# Balance.net
KiCad netlist of a schematic drawn in Altium Designer
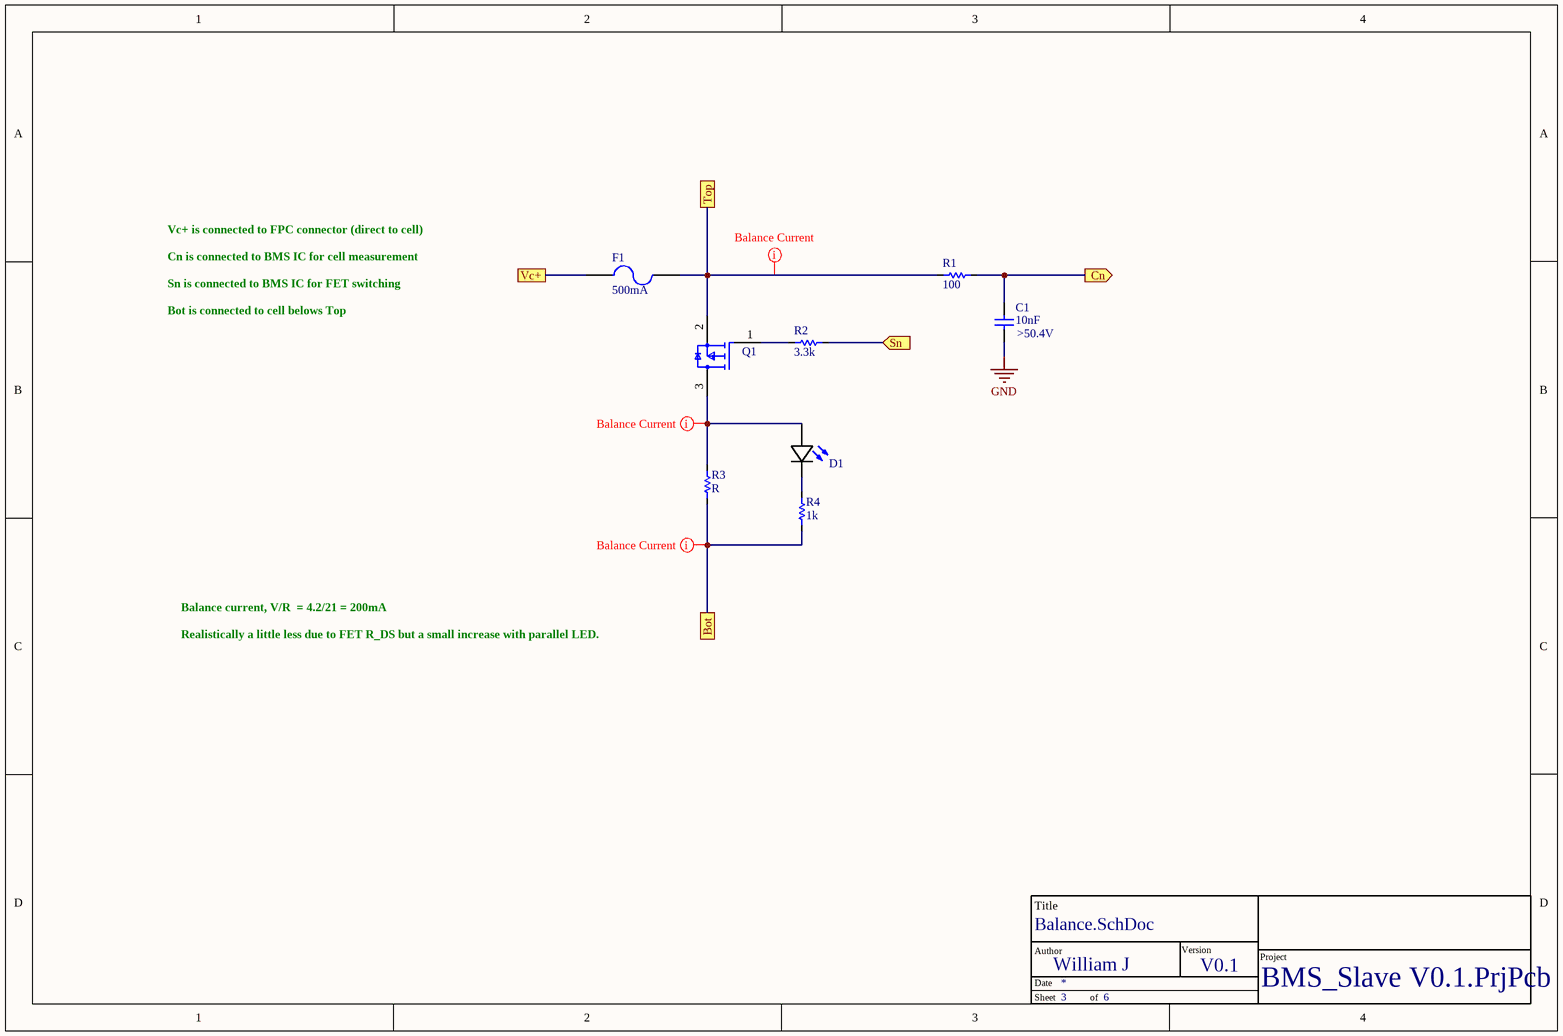
[diagram p0: Balance.SchDoc]

(export (version "E")
  (design (tool "Eeschema 10.0.6"))
  (components
    (comp (ref "*") (value "TitleBlock") (libsource (lib "SchematicLib") (part "TitleBlock")))
    (comp (ref "C1")
      (value "10nF")
      (footprint "C_0603")
      (description "Capacitor")
      (fields (field (name "VOLTAGE") ">50.4V") (field (name "Comment") "C"))
      (libsource (lib "Passives") (part "Capacitor"))
    )
    (comp (ref "D1")
      (value "150060BS55040")
      (footprint "LED (0603)")
      (description "LED BLUE DIFFUSED 0603 SMD")
      (fields (field (name "MANUFACTURER") "Wurth Electronics"))
      (libsource (lib "LEDLib") (part "150060BS55040"))
    )
    (comp (ref "F1")
      (value "0466.500NR")
      (footprint "0466.500NR")
      (fields
        (field (name "MANUFACTURER") "Littelfuse")
        (field (name "CURRENT RATING") "500mA")
        (field (name "PUBLISHER") "Altium Limited")
      )
      (libsource (lib "Miscellaneous Devices") (part "Fuse 2"))
    )
    (comp (ref "Q1")
      (value "NX2301P,215")
      (footprint "FP-SOT23-MFG")
      (description "MOSFET P-CH 20V 2A TO-236AB")
      (libsource (lib "Altium Content Vault") (part "882370683d780ecf8f33bea6fe01d97"))
    )
    (comp (ref "R1")
      (value "100")
      (footprint "R-0603")
      (description "Resistor")
      (libsource (lib "Passives") (part "Resistor"))
    )
    (comp (ref "R2")
      (value "3.3k")
      (footprint "R-0603")
      (description "Resistor")
      (libsource (lib "Passives") (part "Resistor"))
    )
    (comp (ref "R3")
      (value "R")
      (footprint "R_2512")
      (description "Resistor")
      (libsource (lib "Passives") (part "Resistor"))
    )
    (comp (ref "R4")
      (value "1k")
      (footprint "R-0603")
      (description "Resistor")
      (libsource (lib "Passives") (part "Resistor"))
    )
  )
  (nets
    (net (code "1") (name "/Bot") (class "Default")
      (node (ref "R3") (pin "1") (pinfunction "1_1") (pintype "passive"))
      (node (ref "R4") (pin "1") (pinfunction "1_1") (pintype "passive"))
    )
    (net (code "2") (name "/Cn") (class "Default")
      (node (ref "C1") (pin "2") (pinfunction "2_2") (pintype "passive"))
      (node (ref "R1") (pin "2") (pinfunction "2_2") (pintype "passive"))
    )
    (net (code "3") (name "/Sn") (class "Default")
      (node (ref "R2") (pin "2") (pinfunction "2_2") (pintype "passive"))
    )
    (net (code "4") (name "/Top") (class "Default")
      (node (ref "F1") (pin "2") (pinfunction "2_2") (pintype "passive"))
      (node (ref "Q1") (pin "2") (pinfunction "S_2") (pintype "passive"))
      (node (ref "R1") (pin "1") (pinfunction "1_1") (pintype "passive"))
    )
    (net (code "5") (name "/Vc+") (class "Default")
      (node (ref "F1") (pin "1") (pinfunction "1_1") (pintype "passive"))
    )
    (net (code "6") (name "GND") (class "Default")
      (node (ref "C1") (pin "1") (pinfunction "1_1") (pintype "passive"))
    )
    (net (code "7") (name "Net-(D1-A)") (class "Default")
      (node (ref "D1") (pin "2") (pinfunction "A_2") (pintype "passive"))
      (node (ref "Q1") (pin "3") (pinfunction "D_3") (pintype "passive"))
      (node (ref "R3") (pin "2") (pinfunction "2_2") (pintype "passive"))
    )
    (net (code "8") (name "Net-(D1-K)") (class "Default")
      (node (ref "D1") (pin "1") (pinfunction "K_1") (pintype "passive"))
      (node (ref "R4") (pin "2") (pinfunction "2_2") (pintype "passive"))
    )
    (net (code "9") (name "Net-(Q1-G)") (class "Default")
      (node (ref "Q1") (pin "1") (pinfunction "G_1") (pintype "passive"))
      (node (ref "R2") (pin "1") (pinfunction "1_1") (pintype "passive"))
    )
  )
)
